# SevenSegClock.net
KiCad netlist of a schematic drawn in EAGLE
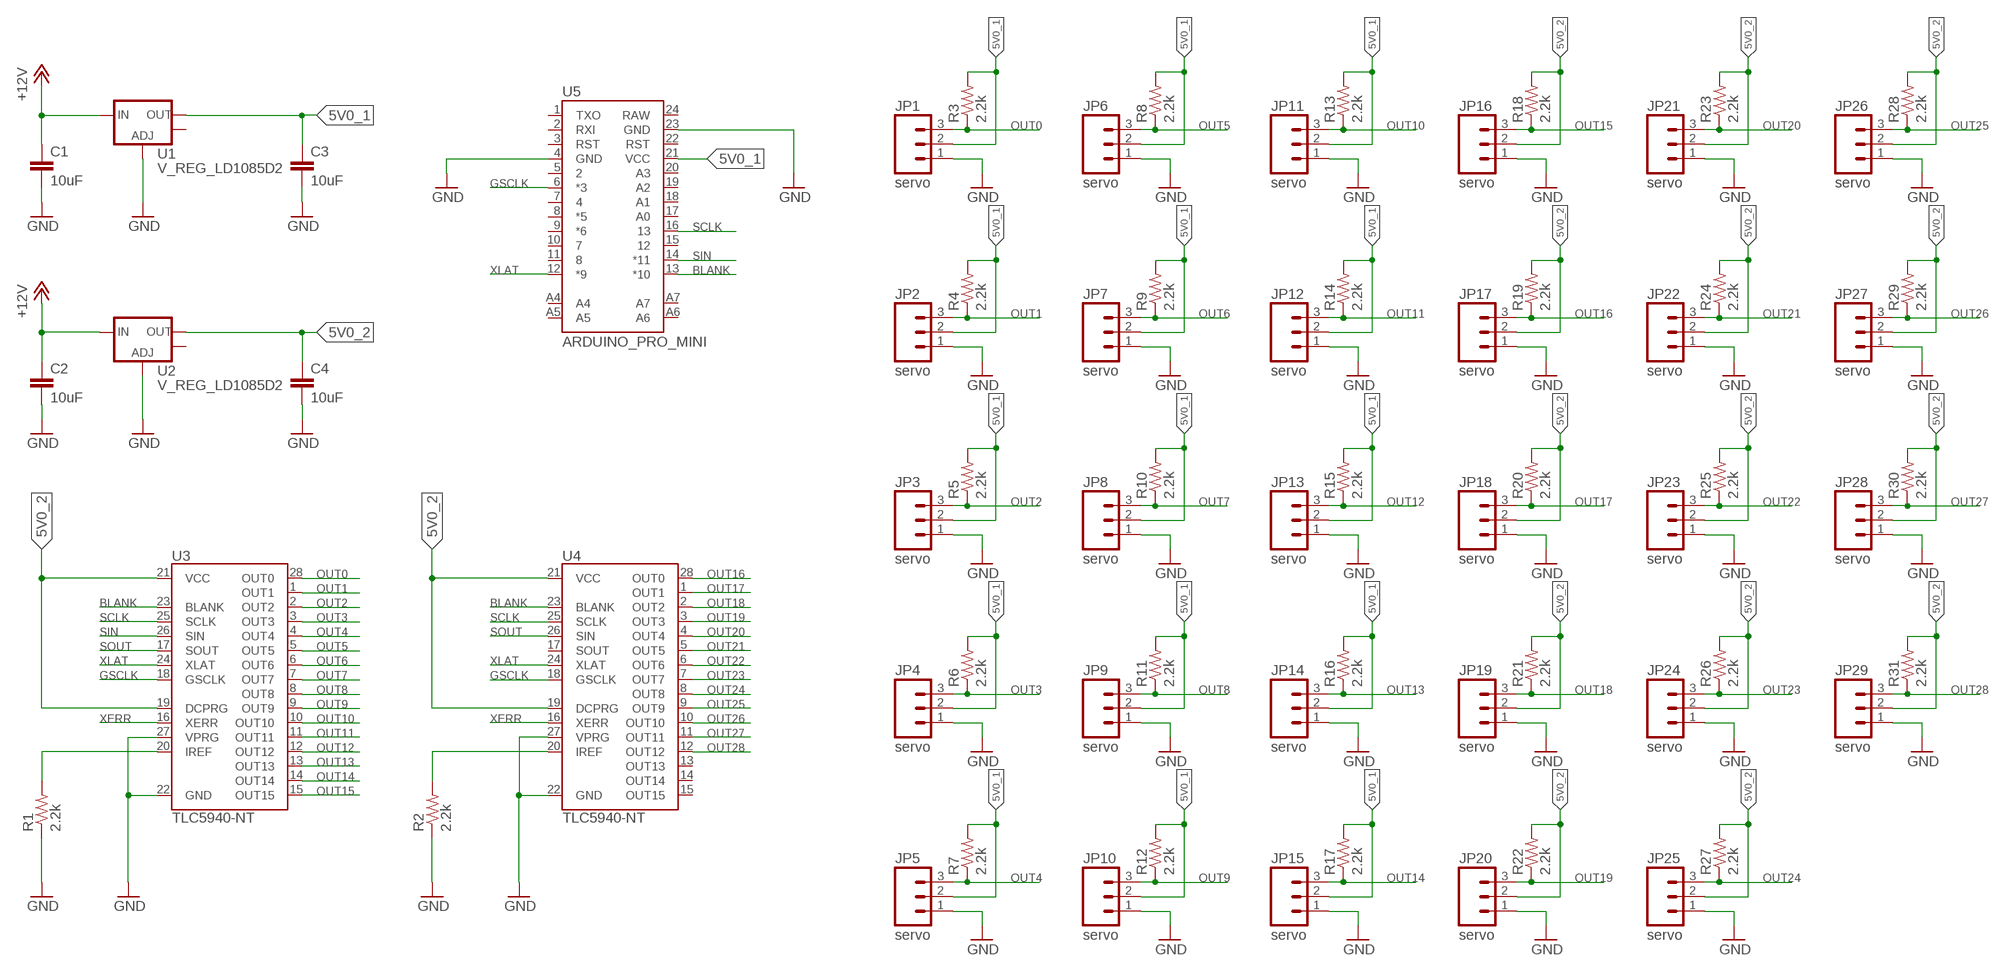
[diagram p0: schematic, sheet 1]

(export (version "E")
  (design (tool "Eeschema 10.0.6"))
  (components
    (comp (ref "C1")
      (value "10uF")
      (footprint "eagle-import:CAP-PTH-5MM")
      (libsource (lib "eagle-import") (part "CAPPTH1"))
    )
    (comp (ref "C2")
      (value "10uF")
      (footprint "eagle-import:CAP-PTH-5MM")
      (libsource (lib "eagle-import") (part "CAPPTH1"))
    )
    (comp (ref "C3")
      (value "10uF")
      (footprint "eagle-import:CAP-PTH-5MM")
      (libsource (lib "eagle-import") (part "CAPPTH1"))
    )
    (comp (ref "C4")
      (value "10uF")
      (footprint "eagle-import:CAP-PTH-5MM")
      (libsource (lib "eagle-import") (part "CAPPTH1"))
    )
    (comp (ref "JP1")
      (value "servo")
      (footprint "eagle-import:1X03")
      (libsource (lib "eagle-import") (part "M03PTH"))
    )
    (comp (ref "JP2")
      (value "servo")
      (footprint "eagle-import:1X03")
      (libsource (lib "eagle-import") (part "M03PTH"))
    )
    (comp (ref "JP3")
      (value "servo")
      (footprint "eagle-import:1X03")
      (libsource (lib "eagle-import") (part "M03PTH"))
    )
    (comp (ref "JP4")
      (value "servo")
      (footprint "eagle-import:1X03")
      (libsource (lib "eagle-import") (part "M03PTH"))
    )
    (comp (ref "JP5")
      (value "servo")
      (footprint "eagle-import:1X03")
      (libsource (lib "eagle-import") (part "M03PTH"))
    )
    (comp (ref "JP6")
      (value "servo")
      (footprint "eagle-import:1X03")
      (libsource (lib "eagle-import") (part "M03PTH"))
    )
    (comp (ref "JP7")
      (value "servo")
      (footprint "eagle-import:1X03")
      (libsource (lib "eagle-import") (part "M03PTH"))
    )
    (comp (ref "JP8")
      (value "servo")
      (footprint "eagle-import:1X03")
      (libsource (lib "eagle-import") (part "M03PTH"))
    )
    (comp (ref "JP9")
      (value "servo")
      (footprint "eagle-import:1X03")
      (libsource (lib "eagle-import") (part "M03PTH"))
    )
    (comp (ref "JP10")
      (value "servo")
      (footprint "eagle-import:1X03")
      (libsource (lib "eagle-import") (part "M03PTH"))
    )
    (comp (ref "JP11")
      (value "servo")
      (footprint "eagle-import:1X03")
      (libsource (lib "eagle-import") (part "M03PTH"))
    )
    (comp (ref "JP12")
      (value "servo")
      (footprint "eagle-import:1X03")
      (libsource (lib "eagle-import") (part "M03PTH"))
    )
    (comp (ref "JP13")
      (value "servo")
      (footprint "eagle-import:1X03")
      (libsource (lib "eagle-import") (part "M03PTH"))
    )
    (comp (ref "JP14")
      (value "servo")
      (footprint "eagle-import:1X03")
      (libsource (lib "eagle-import") (part "M03PTH"))
    )
    (comp (ref "JP15")
      (value "servo")
      (footprint "eagle-import:1X03")
      (libsource (lib "eagle-import") (part "M03PTH"))
    )
    (comp (ref "JP16")
      (value "servo")
      (footprint "eagle-import:1X03")
      (libsource (lib "eagle-import") (part "M03PTH"))
    )
    (comp (ref "JP17")
      (value "servo")
      (footprint "eagle-import:1X03")
      (libsource (lib "eagle-import") (part "M03PTH"))
    )
    (comp (ref "JP18")
      (value "servo")
      (footprint "eagle-import:1X03")
      (libsource (lib "eagle-import") (part "M03PTH"))
    )
    (comp (ref "JP19")
      (value "servo")
      (footprint "eagle-import:1X03")
      (libsource (lib "eagle-import") (part "M03PTH"))
    )
    (comp (ref "JP20")
      (value "servo")
      (footprint "eagle-import:1X03")
      (libsource (lib "eagle-import") (part "M03PTH"))
    )
    (comp (ref "JP21")
      (value "servo")
      (footprint "eagle-import:1X03")
      (libsource (lib "eagle-import") (part "M03PTH"))
    )
    (comp (ref "JP22")
      (value "servo")
      (footprint "eagle-import:1X03")
      (libsource (lib "eagle-import") (part "M03PTH"))
    )
    (comp (ref "JP23")
      (value "servo")
      (footprint "eagle-import:1X03")
      (libsource (lib "eagle-import") (part "M03PTH"))
    )
    (comp (ref "JP24")
      (value "servo")
      (footprint "eagle-import:1X03")
      (libsource (lib "eagle-import") (part "M03PTH"))
    )
    (comp (ref "JP25")
      (value "servo")
      (footprint "eagle-import:1X03")
      (libsource (lib "eagle-import") (part "M03PTH"))
    )
    (comp (ref "JP26")
      (value "servo")
      (footprint "eagle-import:1X03")
      (libsource (lib "eagle-import") (part "M03PTH"))
    )
    (comp (ref "JP27")
      (value "servo")
      (footprint "eagle-import:1X03")
      (libsource (lib "eagle-import") (part "M03PTH"))
    )
    (comp (ref "JP28")
      (value "servo")
      (footprint "eagle-import:1X03")
      (libsource (lib "eagle-import") (part "M03PTH"))
    )
    (comp (ref "JP29")
      (value "servo")
      (footprint "eagle-import:1X03")
      (libsource (lib "eagle-import") (part "M03PTH"))
    )
    (comp (ref "R1")
      (value "2.2k")
      (footprint "eagle-import:0204_5")
      (libsource (lib "eagle-import") (part "R-US_0204/5"))
    )
    (comp (ref "R2")
      (value "2.2k")
      (footprint "eagle-import:0204_5")
      (libsource (lib "eagle-import") (part "R-US_0204/5"))
    )
    (comp (ref "R3")
      (value "2.2k")
      (footprint "eagle-import:0204_5")
      (libsource (lib "eagle-import") (part "R-US_0204/5"))
    )
    (comp (ref "R4")
      (value "2.2k")
      (footprint "eagle-import:0204_5")
      (libsource (lib "eagle-import") (part "R-US_0204/5"))
    )
    (comp (ref "R5")
      (value "2.2k")
      (footprint "eagle-import:0204_5")
      (libsource (lib "eagle-import") (part "R-US_0204/5"))
    )
    (comp (ref "R6")
      (value "2.2k")
      (footprint "eagle-import:0204_5")
      (libsource (lib "eagle-import") (part "R-US_0204/5"))
    )
    (comp (ref "R7")
      (value "2.2k")
      (footprint "eagle-import:0204_5")
      (libsource (lib "eagle-import") (part "R-US_0204/5"))
    )
    (comp (ref "R8")
      (value "2.2k")
      (footprint "eagle-import:0204_5")
      (libsource (lib "eagle-import") (part "R-US_0204/5"))
    )
    (comp (ref "R9")
      (value "2.2k")
      (footprint "eagle-import:0204_5")
      (libsource (lib "eagle-import") (part "R-US_0204/5"))
    )
    (comp (ref "R10")
      (value "2.2k")
      (footprint "eagle-import:0204_5")
      (libsource (lib "eagle-import") (part "R-US_0204/5"))
    )
    (comp (ref "R11")
      (value "2.2k")
      (footprint "eagle-import:0204_5")
      (libsource (lib "eagle-import") (part "R-US_0204/5"))
    )
    (comp (ref "R12")
      (value "2.2k")
      (footprint "eagle-import:0204_5")
      (libsource (lib "eagle-import") (part "R-US_0204/5"))
    )
    (comp (ref "R13")
      (value "2.2k")
      (footprint "eagle-import:0204_5")
      (libsource (lib "eagle-import") (part "R-US_0204/5"))
    )
    (comp (ref "R14")
      (value "2.2k")
      (footprint "eagle-import:0204_5")
      (libsource (lib "eagle-import") (part "R-US_0204/5"))
    )
    (comp (ref "R15")
      (value "2.2k")
      (footprint "eagle-import:0204_5")
      (libsource (lib "eagle-import") (part "R-US_0204/5"))
    )
    (comp (ref "R16")
      (value "2.2k")
      (footprint "eagle-import:0204_5")
      (libsource (lib "eagle-import") (part "R-US_0204/5"))
    )
    (comp (ref "R17")
      (value "2.2k")
      (footprint "eagle-import:0204_5")
      (libsource (lib "eagle-import") (part "R-US_0204/5"))
    )
    (comp (ref "R18")
      (value "2.2k")
      (footprint "eagle-import:0204_5")
      (libsource (lib "eagle-import") (part "R-US_0204/5"))
    )
    (comp (ref "R19")
      (value "2.2k")
      (footprint "eagle-import:0204_5")
      (libsource (lib "eagle-import") (part "R-US_0204/5"))
    )
    (comp (ref "R20")
      (value "2.2k")
      (footprint "eagle-import:0204_5")
      (libsource (lib "eagle-import") (part "R-US_0204/5"))
    )
    (comp (ref "R21")
      (value "2.2k")
      (footprint "eagle-import:0204_5")
      (libsource (lib "eagle-import") (part "R-US_0204/5"))
    )
    (comp (ref "R22")
      (value "2.2k")
      (footprint "eagle-import:0204_5")
      (libsource (lib "eagle-import") (part "R-US_0204/5"))
    )
    (comp (ref "R23")
      (value "2.2k")
      (footprint "eagle-import:0204_5")
      (libsource (lib "eagle-import") (part "R-US_0204/5"))
    )
    (comp (ref "R24")
      (value "2.2k")
      (footprint "eagle-import:0204_5")
      (libsource (lib "eagle-import") (part "R-US_0204/5"))
    )
    (comp (ref "R25")
      (value "2.2k")
      (footprint "eagle-import:0204_5")
      (libsource (lib "eagle-import") (part "R-US_0204/5"))
    )
    (comp (ref "R26")
      (value "2.2k")
      (footprint "eagle-import:0204_5")
      (libsource (lib "eagle-import") (part "R-US_0204/5"))
    )
    (comp (ref "R27")
      (value "2.2k")
      (footprint "eagle-import:0204_5")
      (libsource (lib "eagle-import") (part "R-US_0204/5"))
    )
    (comp (ref "R28")
      (value "2.2k")
      (footprint "eagle-import:0204_5")
      (libsource (lib "eagle-import") (part "R-US_0204/5"))
    )
    (comp (ref "R29")
      (value "2.2k")
      (footprint "eagle-import:0204_5")
      (libsource (lib "eagle-import") (part "R-US_0204/5"))
    )
    (comp (ref "R30")
      (value "2.2k")
      (footprint "eagle-import:0204_5")
      (libsource (lib "eagle-import") (part "R-US_0204/5"))
    )
    (comp (ref "R31")
      (value "2.2k")
      (footprint "eagle-import:0204_5")
      (libsource (lib "eagle-import") (part "R-US_0204/5"))
    )
    (comp (ref "U1")
      (value "V_REG_LD1085D2")
      (footprint "eagle-import:D2PACK_A")
      (libsource (lib "eagle-import") (part "V_REG_LD1085D2"))
    )
    (comp (ref "U2")
      (value "V_REG_LD1085D2")
      (footprint "eagle-import:D2PACK_A")
      (libsource (lib "eagle-import") (part "V_REG_LD1085D2"))
    )
    (comp (ref "U3")
      (value "TLC5940-NT")
      (footprint "eagle-import:DIL28-3")
      (libsource (lib "eagle-import") (part "TLC5940-NT"))
    )
    (comp (ref "U4")
      (value "TLC5940-NT")
      (footprint "eagle-import:DIL28-3")
      (libsource (lib "eagle-import") (part "TLC5940-NT"))
    )
    (comp (ref "U5")
      (value "ARDUINO_PRO_MINI")
      (footprint "eagle-import:ARDUINO_PRO_MINI")
      (libsource (lib "eagle-import") (part "ARDUINO_PRO_MINI"))
    )
  )
  (nets
    (net (code "1") (name "+12V") (class "Default")
      (node (ref "C1") (pin "1") (pinfunction "1_1") (pintype "passive"))
      (node (ref "C2") (pin "1") (pinfunction "1_1") (pintype "passive"))
      (node (ref "U1") (pin "3") (pinfunction "IN_3") (pintype "input"))
      (node (ref "U2") (pin "3") (pinfunction "IN_3") (pintype "input"))
    )
    (net (code "2") (name "/BLANK") (class "Default")
      (node (ref "U3") (pin "23") (pinfunction "BLANK_23") (pintype "bidirectional"))
      (node (ref "U4") (pin "23") (pinfunction "BLANK_23") (pintype "bidirectional"))
      (node (ref "U5") (pin "13") (pinfunction "*10_13") (pintype "bidirectional"))
    )
    (net (code "3") (name "/GSCLK") (class "Default")
      (node (ref "U3") (pin "18") (pinfunction "GSCLK_18") (pintype "bidirectional"))
      (node (ref "U4") (pin "18") (pinfunction "GSCLK_18") (pintype "bidirectional"))
      (node (ref "U5") (pin "6") (pinfunction "*3_6") (pintype "bidirectional"))
    )
    (net (code "4") (name "/OUT0") (class "Default")
      (node (ref "JP1") (pin "3") (pinfunction "3_3") (pintype "passive"))
      (node (ref "R3") (pin "1") (pinfunction "1_1") (pintype "passive"))
      (node (ref "U3") (pin "28") (pinfunction "OUT0_28") (pintype "bidirectional"))
    )
    (net (code "5") (name "/OUT1") (class "Default")
      (node (ref "JP2") (pin "3") (pinfunction "3_3") (pintype "passive"))
      (node (ref "R4") (pin "1") (pinfunction "1_1") (pintype "passive"))
      (node (ref "U3") (pin "1") (pinfunction "OUT1_1") (pintype "bidirectional"))
    )
    (net (code "6") (name "/OUT2") (class "Default")
      (node (ref "JP3") (pin "3") (pinfunction "3_3") (pintype "passive"))
      (node (ref "R5") (pin "1") (pinfunction "1_1") (pintype "passive"))
      (node (ref "U3") (pin "2") (pinfunction "OUT2_2") (pintype "bidirectional"))
    )
    (net (code "7") (name "/OUT3") (class "Default")
      (node (ref "JP4") (pin "3") (pinfunction "3_3") (pintype "passive"))
      (node (ref "R6") (pin "1") (pinfunction "1_1") (pintype "passive"))
      (node (ref "U3") (pin "3") (pinfunction "OUT3_3") (pintype "bidirectional"))
    )
    (net (code "8") (name "/OUT4") (class "Default")
      (node (ref "JP5") (pin "3") (pinfunction "3_3") (pintype "passive"))
      (node (ref "R7") (pin "1") (pinfunction "1_1") (pintype "passive"))
      (node (ref "U3") (pin "4") (pinfunction "OUT4_4") (pintype "bidirectional"))
    )
    (net (code "9") (name "/OUT5") (class "Default")
      (node (ref "JP6") (pin "3") (pinfunction "3_3") (pintype "passive"))
      (node (ref "R8") (pin "1") (pinfunction "1_1") (pintype "passive"))
      (node (ref "U3") (pin "5") (pinfunction "OUT5_5") (pintype "bidirectional"))
    )
    (net (code "10") (name "/OUT6") (class "Default")
      (node (ref "JP7") (pin "3") (pinfunction "3_3") (pintype "passive"))
      (node (ref "R9") (pin "1") (pinfunction "1_1") (pintype "passive"))
      (node (ref "U3") (pin "6") (pinfunction "OUT6_6") (pintype "bidirectional"))
    )
    (net (code "11") (name "/OUT7") (class "Default")
      (node (ref "JP8") (pin "3") (pinfunction "3_3") (pintype "passive"))
      (node (ref "R10") (pin "1") (pinfunction "1_1") (pintype "passive"))
      (node (ref "U3") (pin "7") (pinfunction "OUT7_7") (pintype "bidirectional"))
    )
    (net (code "12") (name "/OUT8") (class "Default")
      (node (ref "JP9") (pin "3") (pinfunction "3_3") (pintype "passive"))
      (node (ref "R11") (pin "1") (pinfunction "1_1") (pintype "passive"))
      (node (ref "U3") (pin "8") (pinfunction "OUT8_8") (pintype "bidirectional"))
    )
    (net (code "13") (name "/OUT9") (class "Default")
      (node (ref "JP10") (pin "3") (pinfunction "3_3") (pintype "passive"))
      (node (ref "R12") (pin "1") (pinfunction "1_1") (pintype "passive"))
      (node (ref "U3") (pin "9") (pinfunction "OUT9_9") (pintype "bidirectional"))
    )
    (net (code "14") (name "/OUT10") (class "Default")
      (node (ref "JP11") (pin "3") (pinfunction "3_3") (pintype "passive"))
      (node (ref "R13") (pin "1") (pinfunction "1_1") (pintype "passive"))
      (node (ref "U3") (pin "10") (pinfunction "OUT10_10") (pintype "bidirectional"))
    )
    (net (code "15") (name "/OUT11") (class "Default")
      (node (ref "JP12") (pin "3") (pinfunction "3_3") (pintype "passive"))
      (node (ref "R14") (pin "1") (pinfunction "1_1") (pintype "passive"))
      (node (ref "U3") (pin "11") (pinfunction "OUT11_11") (pintype "bidirectional"))
    )
    (net (code "16") (name "/OUT12") (class "Default")
      (node (ref "JP13") (pin "3") (pinfunction "3_3") (pintype "passive"))
      (node (ref "R15") (pin "1") (pinfunction "1_1") (pintype "passive"))
      (node (ref "U3") (pin "12") (pinfunction "OUT12_12") (pintype "bidirectional"))
    )
    (net (code "17") (name "/OUT13") (class "Default")
      (node (ref "JP14") (pin "3") (pinfunction "3_3") (pintype "passive"))
      (node (ref "R16") (pin "1") (pinfunction "1_1") (pintype "passive"))
      (node (ref "U3") (pin "13") (pinfunction "OUT13_13") (pintype "bidirectional"))
    )
    (net (code "18") (name "/OUT14") (class "Default")
      (node (ref "JP15") (pin "3") (pinfunction "3_3") (pintype "passive"))
      (node (ref "R17") (pin "1") (pinfunction "1_1") (pintype "passive"))
      (node (ref "U3") (pin "14") (pinfunction "OUT14_14") (pintype "bidirectional"))
    )
    (net (code "19") (name "/OUT15") (class "Default")
      (node (ref "JP16") (pin "3") (pinfunction "3_3") (pintype "passive"))
      (node (ref "R18") (pin "1") (pinfunction "1_1") (pintype "passive"))
      (node (ref "U3") (pin "15") (pinfunction "OUT15_15") (pintype "bidirectional"))
    )
    (net (code "20") (name "/OUT16") (class "Default")
      (node (ref "JP17") (pin "3") (pinfunction "3_3") (pintype "passive"))
      (node (ref "R19") (pin "1") (pinfunction "1_1") (pintype "passive"))
      (node (ref "U4") (pin "28") (pinfunction "OUT0_28") (pintype "bidirectional"))
    )
    (net (code "21") (name "/OUT17") (class "Default")
      (node (ref "JP18") (pin "3") (pinfunction "3_3") (pintype "passive"))
      (node (ref "R20") (pin "1") (pinfunction "1_1") (pintype "passive"))
      (node (ref "U4") (pin "1") (pinfunction "OUT1_1") (pintype "bidirectional"))
    )
    (net (code "22") (name "/OUT18") (class "Default")
      (node (ref "JP19") (pin "3") (pinfunction "3_3") (pintype "passive"))
      (node (ref "R21") (pin "1") (pinfunction "1_1") (pintype "passive"))
      (node (ref "U4") (pin "2") (pinfunction "OUT2_2") (pintype "bidirectional"))
    )
    (net (code "23") (name "/OUT19") (class "Default")
      (node (ref "JP20") (pin "3") (pinfunction "3_3") (pintype "passive"))
      (node (ref "R22") (pin "1") (pinfunction "1_1") (pintype "passive"))
      (node (ref "U4") (pin "3") (pinfunction "OUT3_3") (pintype "bidirectional"))
    )
    (net (code "24") (name "/OUT20") (class "Default")
      (node (ref "JP21") (pin "3") (pinfunction "3_3") (pintype "passive"))
      (node (ref "R23") (pin "1") (pinfunction "1_1") (pintype "passive"))
      (node (ref "U4") (pin "4") (pinfunction "OUT4_4") (pintype "bidirectional"))
    )
    (net (code "25") (name "/OUT21") (class "Default")
      (node (ref "JP22") (pin "3") (pinfunction "3_3") (pintype "passive"))
      (node (ref "R24") (pin "1") (pinfunction "1_1") (pintype "passive"))
      (node (ref "U4") (pin "5") (pinfunction "OUT5_5") (pintype "bidirectional"))
    )
    (net (code "26") (name "/OUT22") (class "Default")
      (node (ref "JP23") (pin "3") (pinfunction "3_3") (pintype "passive"))
      (node (ref "R25") (pin "1") (pinfunction "1_1") (pintype "passive"))
      (node (ref "U4") (pin "6") (pinfunction "OUT6_6") (pintype "bidirectional"))
    )
    (net (code "27") (name "/OUT23") (class "Default")
      (node (ref "JP24") (pin "3") (pinfunction "3_3") (pintype "passive"))
      (node (ref "R26") (pin "1") (pinfunction "1_1") (pintype "passive"))
      (node (ref "U4") (pin "7") (pinfunction "OUT7_7") (pintype "bidirectional"))
    )
    (net (code "28") (name "/OUT24") (class "Default")
      (node (ref "JP25") (pin "3") (pinfunction "3_3") (pintype "passive"))
      (node (ref "R27") (pin "1") (pinfunction "1_1") (pintype "passive"))
      (node (ref "U4") (pin "8") (pinfunction "OUT8_8") (pintype "bidirectional"))
    )
    (net (code "29") (name "/OUT25") (class "Default")
      (node (ref "JP26") (pin "3") (pinfunction "3_3") (pintype "passive"))
      (node (ref "R28") (pin "1") (pinfunction "1_1") (pintype "passive"))
      (node (ref "U4") (pin "9") (pinfunction "OUT9_9") (pintype "bidirectional"))
    )
    (net (code "30") (name "/OUT26") (class "Default")
      (node (ref "JP27") (pin "3") (pinfunction "3_3") (pintype "passive"))
      (node (ref "R29") (pin "1") (pinfunction "1_1") (pintype "passive"))
      (node (ref "U4") (pin "10") (pinfunction "OUT10_10") (pintype "bidirectional"))
    )
    (net (code "31") (name "/OUT27") (class "Default")
      (node (ref "JP28") (pin "3") (pinfunction "3_3") (pintype "passive"))
      (node (ref "R30") (pin "1") (pinfunction "1_1") (pintype "passive"))
      (node (ref "U4") (pin "11") (pinfunction "OUT11_11") (pintype "bidirectional"))
    )
    (net (code "32") (name "/OUT28") (class "Default")
      (node (ref "JP29") (pin "3") (pinfunction "3_3") (pintype "passive"))
      (node (ref "R31") (pin "1") (pinfunction "1_1") (pintype "passive"))
      (node (ref "U4") (pin "12") (pinfunction "OUT12_12") (pintype "bidirectional"))
    )
    (net (code "33") (name "/SCLK") (class "Default")
      (node (ref "U3") (pin "25") (pinfunction "SCLK_25") (pintype "bidirectional"))
      (node (ref "U4") (pin "25") (pinfunction "SCLK_25") (pintype "bidirectional"))
      (node (ref "U5") (pin "16") (pinfunction "13_16") (pintype "bidirectional"))
    )
    (net (code "34") (name "/SIN") (class "Default")
      (node (ref "U3") (pin "26") (pinfunction "SIN_26") (pintype "bidirectional"))
      (node (ref "U5") (pin "14") (pinfunction "*11_14") (pintype "bidirectional"))
    )
    (net (code "35") (name "/SOUT") (class "Default")
      (node (ref "U3") (pin "17") (pinfunction "SOUT_17") (pintype "bidirectional"))
      (node (ref "U4") (pin "26") (pinfunction "SIN_26") (pintype "bidirectional"))
    )
    (net (code "36") (name "/XERR") (class "Default")
      (node (ref "U3") (pin "16") (pinfunction "XERR_16") (pintype "bidirectional"))
      (node (ref "U4") (pin "16") (pinfunction "XERR_16") (pintype "bidirectional"))
    )
    (net (code "37") (name "/XLAT") (class "Default")
      (node (ref "U3") (pin "24") (pinfunction "XLAT_24") (pintype "bidirectional"))
      (node (ref "U4") (pin "24") (pinfunction "XLAT_24") (pintype "bidirectional"))
      (node (ref "U5") (pin "12") (pinfunction "*9_12") (pintype "bidirectional"))
    )
    (net (code "38") (name "5V0_1") (class "Default")
      (node (ref "C3") (pin "1") (pinfunction "1_1") (pintype "passive"))
      (node (ref "JP1") (pin "2") (pinfunction "2_2") (pintype "passive"))
      (node (ref "JP10") (pin "2") (pinfunction "2_2") (pintype "passive"))
      (node (ref "JP11") (pin "2") (pinfunction "2_2") (pintype "passive"))
      (node (ref "JP12") (pin "2") (pinfunction "2_2") (pintype "passive"))
      (node (ref "JP13") (pin "2") (pinfunction "2_2") (pintype "passive"))
      (node (ref "JP14") (pin "2") (pinfunction "2_2") (pintype "passive"))
      (node (ref "JP15") (pin "2") (pinfunction "2_2") (pintype "passive"))
      (node (ref "JP2") (pin "2") (pinfunction "2_2") (pintype "passive"))
      (node (ref "JP3") (pin "2") (pinfunction "2_2") (pintype "passive"))
      (node (ref "JP4") (pin "2") (pinfunction "2_2") (pintype "passive"))
      (node (ref "JP5") (pin "2") (pinfunction "2_2") (pintype "passive"))
      (node (ref "JP6") (pin "2") (pinfunction "2_2") (pintype "passive"))
      (node (ref "JP7") (pin "2") (pinfunction "2_2") (pintype "passive"))
      (node (ref "JP8") (pin "2") (pinfunction "2_2") (pintype "passive"))
      (node (ref "JP9") (pin "2") (pinfunction "2_2") (pintype "passive"))
      (node (ref "R10") (pin "2") (pinfunction "2_2") (pintype "passive"))
      (node (ref "R11") (pin "2") (pinfunction "2_2") (pintype "passive"))
      (node (ref "R12") (pin "2") (pinfunction "2_2") (pintype "passive"))
      (node (ref "R13") (pin "2") (pinfunction "2_2") (pintype "passive"))
      (node (ref "R14") (pin "2") (pinfunction "2_2") (pintype "passive"))
      (node (ref "R15") (pin "2") (pinfunction "2_2") (pintype "passive"))
      (node (ref "R16") (pin "2") (pinfunction "2_2") (pintype "passive"))
      (node (ref "R17") (pin "2") (pinfunction "2_2") (pintype "passive"))
      (node (ref "R3") (pin "2") (pinfunction "2_2") (pintype "passive"))
      (node (ref "R4") (pin "2") (pinfunction "2_2") (pintype "passive"))
      (node (ref "R5") (pin "2") (pinfunction "2_2") (pintype "passive"))
      (node (ref "R6") (pin "2") (pinfunction "2_2") (pintype "passive"))
      (node (ref "R7") (pin "2") (pinfunction "2_2") (pintype "passive"))
      (node (ref "R8") (pin "2") (pinfunction "2_2") (pintype "passive"))
      (node (ref "R9") (pin "2") (pinfunction "2_2") (pintype "passive"))
      (node (ref "U1") (pin "2") (pinfunction "OUT_2") (pintype "output"))
      (node (ref "U5") (pin "21") (pinfunction "VCC_21") (pintype "bidirectional"))
    )
    (net (code "39") (name "5V0_2") (class "Default")
      (node (ref "C4") (pin "1") (pinfunction "1_1") (pintype "passive"))
      (node (ref "JP16") (pin "2") (pinfunction "2_2") (pintype "passive"))
      (node (ref "JP17") (pin "2") (pinfunction "2_2") (pintype "passive"))
      (node (ref "JP18") (pin "2") (pinfunction "2_2") (pintype "passive"))
      (node (ref "JP19") (pin "2") (pinfunction "2_2") (pintype "passive"))
      (node (ref "JP20") (pin "2") (pinfunction "2_2") (pintype "passive"))
      (node (ref "JP21") (pin "2") (pinfunction "2_2") (pintype "passive"))
      (node (ref "JP22") (pin "2") (pinfunction "2_2") (pintype "passive"))
      (node (ref "JP23") (pin "2") (pinfunction "2_2") (pintype "passive"))
      (node (ref "JP24") (pin "2") (pinfunction "2_2") (pintype "passive"))
      (node (ref "JP25") (pin "2") (pinfunction "2_2") (pintype "passive"))
      (node (ref "JP26") (pin "2") (pinfunction "2_2") (pintype "passive"))
      (node (ref "JP27") (pin "2") (pinfunction "2_2") (pintype "passive"))
      (node (ref "JP28") (pin "2") (pinfunction "2_2") (pintype "passive"))
      (node (ref "JP29") (pin "2") (pinfunction "2_2") (pintype "passive"))
      (node (ref "R18") (pin "2") (pinfunction "2_2") (pintype "passive"))
      (node (ref "R19") (pin "2") (pinfunction "2_2") (pintype "passive"))
      (node (ref "R20") (pin "2") (pinfunction "2_2") (pintype "passive"))
      (node (ref "R21") (pin "2") (pinfunction "2_2") (pintype "passive"))
      (node (ref "R22") (pin "2") (pinfunction "2_2") (pintype "passive"))
      (node (ref "R23") (pin "2") (pinfunction "2_2") (pintype "passive"))
      (node (ref "R24") (pin "2") (pinfunction "2_2") (pintype "passive"))
      (node (ref "R25") (pin "2") (pinfunction "2_2") (pintype "passive"))
      (node (ref "R26") (pin "2") (pinfunction "2_2") (pintype "passive"))
      (node (ref "R27") (pin "2") (pinfunction "2_2") (pintype "passive"))
      (node (ref "R28") (pin "2") (pinfunction "2_2") (pintype "passive"))
      (node (ref "R29") (pin "2") (pinfunction "2_2") (pintype "passive"))
      (node (ref "R30") (pin "2") (pinfunction "2_2") (pintype "passive"))
      (node (ref "R31") (pin "2") (pinfunction "2_2") (pintype "passive"))
      (node (ref "U2") (pin "2") (pinfunction "OUT_2") (pintype "output"))
      (node (ref "U3") (pin "19") (pinfunction "DCPRG_19") (pintype "bidirectional"))
      (node (ref "U3") (pin "21") (pinfunction "VCC_21") (pintype "bidirectional"))
      (node (ref "U4") (pin "19") (pinfunction "DCPRG_19") (pintype "bidirectional"))
      (node (ref "U4") (pin "21") (pinfunction "VCC_21") (pintype "bidirectional"))
    )
    (net (code "40") (name "GND") (class "Default")
      (node (ref "C1") (pin "2") (pinfunction "2_2") (pintype "passive"))
      (node (ref "C2") (pin "2") (pinfunction "2_2") (pintype "passive"))
      (node (ref "C3") (pin "2") (pinfunction "2_2") (pintype "passive"))
      (node (ref "C4") (pin "2") (pinfunction "2_2") (pintype "passive"))
      (node (ref "JP1") (pin "1") (pinfunction "1_1") (pintype "passive"))
      (node (ref "JP10") (pin "1") (pinfunction "1_1") (pintype "passive"))
      (node (ref "JP11") (pin "1") (pinfunction "1_1") (pintype "passive"))
      (node (ref "JP12") (pin "1") (pinfunction "1_1") (pintype "passive"))
      (node (ref "JP13") (pin "1") (pinfunction "1_1") (pintype "passive"))
      (node (ref "JP14") (pin "1") (pinfunction "1_1") (pintype "passive"))
      (node (ref "JP15") (pin "1") (pinfunction "1_1") (pintype "passive"))
      (node (ref "JP16") (pin "1") (pinfunction "1_1") (pintype "passive"))
      (node (ref "JP17") (pin "1") (pinfunction "1_1") (pintype "passive"))
      (node (ref "JP18") (pin "1") (pinfunction "1_1") (pintype "passive"))
      (node (ref "JP19") (pin "1") (pinfunction "1_1") (pintype "passive"))
      (node (ref "JP2") (pin "1") (pinfunction "1_1") (pintype "passive"))
      (node (ref "JP20") (pin "1") (pinfunction "1_1") (pintype "passive"))
      (node (ref "JP21") (pin "1") (pinfunction "1_1") (pintype "passive"))
      (node (ref "JP22") (pin "1") (pinfunction "1_1") (pintype "passive"))
      (node (ref "JP23") (pin "1") (pinfunction "1_1") (pintype "passive"))
      (node (ref "JP24") (pin "1") (pinfunction "1_1") (pintype "passive"))
      (node (ref "JP25") (pin "1") (pinfunction "1_1") (pintype "passive"))
      (node (ref "JP26") (pin "1") (pinfunction "1_1") (pintype "passive"))
      (node (ref "JP27") (pin "1") (pinfunction "1_1") (pintype "passive"))
      (node (ref "JP28") (pin "1") (pinfunction "1_1") (pintype "passive"))
      (node (ref "JP29") (pin "1") (pinfunction "1_1") (pintype "passive"))
      (node (ref "JP3") (pin "1") (pinfunction "1_1") (pintype "passive"))
      (node (ref "JP4") (pin "1") (pinfunction "1_1") (pintype "passive"))
      (node (ref "JP5") (pin "1") (pinfunction "1_1") (pintype "passive"))
      (node (ref "JP6") (pin "1") (pinfunction "1_1") (pintype "passive"))
      (node (ref "JP7") (pin "1") (pinfunction "1_1") (pintype "passive"))
      (node (ref "JP8") (pin "1") (pinfunction "1_1") (pintype "passive"))
      (node (ref "JP9") (pin "1") (pinfunction "1_1") (pintype "passive"))
      (node (ref "R1") (pin "1") (pinfunction "1_1") (pintype "passive"))
      (node (ref "R2") (pin "1") (pinfunction "1_1") (pintype "passive"))
      (node (ref "U1") (pin "1") (pinfunction "ADJ_1") (pintype "input"))
      (node (ref "U2") (pin "1") (pinfunction "ADJ_1") (pintype "input"))
      (node (ref "U3") (pin "22") (pinfunction "GND_22") (pintype "bidirectional"))
      (node (ref "U3") (pin "27") (pinfunction "VPRG_27") (pintype "bidirectional"))
      (node (ref "U4") (pin "22") (pinfunction "GND_22") (pintype "bidirectional"))
      (node (ref "U4") (pin "27") (pinfunction "VPRG_27") (pintype "bidirectional"))
      (node (ref "U5") (pin "23") (pinfunction "GND_23") (pintype "bidirectional"))
      (node (ref "U5") (pin "4") (pinfunction "GND_4") (pintype "bidirectional"))
    )
    (net (code "41") (name "Net-(U3-IREF)") (class "Default")
      (node (ref "R1") (pin "2") (pinfunction "2_2") (pintype "passive"))
      (node (ref "U3") (pin "20") (pinfunction "IREF_20") (pintype "bidirectional"))
    )
    (net (code "42") (name "Net-(U4-IREF)") (class "Default")
      (node (ref "R2") (pin "2") (pinfunction "2_2") (pintype "passive"))
      (node (ref "U4") (pin "20") (pinfunction "IREF_20") (pintype "bidirectional"))
    )
    (net (code "43") (name "unconnected-(U1-OUT-PadTAB)") (class "Default")
      (node (ref "U1") (pin "TAB") (pinfunction "OUT_TAB") (pintype "output"))
    )
    (net (code "44") (name "unconnected-(U2-OUT-PadTAB)") (class "Default")
      (node (ref "U2") (pin "TAB") (pinfunction "OUT_TAB") (pintype "output"))
    )
    (net (code "45") (name "unconnected-(U4-OUT13-Pad13)") (class "Default")
      (node (ref "U4") (pin "13") (pinfunction "OUT13_13") (pintype "bidirectional"))
    )
    (net (code "46") (name "unconnected-(U4-OUT14-Pad14)") (class "Default")
      (node (ref "U4") (pin "14") (pinfunction "OUT14_14") (pintype "bidirectional"))
    )
    (net (code "47") (name "unconnected-(U4-OUT15-Pad15)") (class "Default")
      (node (ref "U4") (pin "15") (pinfunction "OUT15_15") (pintype "bidirectional"))
    )
    (net (code "48") (name "unconnected-(U4-SOUT-Pad17)") (class "Default")
      (node (ref "U4") (pin "17") (pinfunction "SOUT_17") (pintype "bidirectional"))
    )
    (net (code "49") (name "unconnected-(U5-*5-Pad8)") (class "Default")
      (node (ref "U5") (pin "8") (pinfunction "*5_8") (pintype "bidirectional"))
    )
    (net (code "50") (name "unconnected-(U5-*6-Pad9)") (class "Default")
      (node (ref "U5") (pin "9") (pinfunction "*6_9") (pintype "bidirectional"))
    )
    (net (code "51") (name "unconnected-(U5-2-Pad5)") (class "Default")
      (node (ref "U5") (pin "5") (pinfunction "2_5") (pintype "bidirectional"))
    )
    (net (code "52") (name "unconnected-(U5-4-Pad7)") (class "Default")
      (node (ref "U5") (pin "7") (pinfunction "4_7") (pintype "bidirectional"))
    )
    (net (code "53") (name "unconnected-(U5-7-Pad10)") (class "Default")
      (node (ref "U5") (pin "10") (pinfunction "7_10") (pintype "bidirectional"))
    )
    (net (code "54") (name "unconnected-(U5-8-Pad11)") (class "Default")
      (node (ref "U5") (pin "11") (pinfunction "8_11") (pintype "bidirectional"))
    )
    (net (code "55") (name "unconnected-(U5-12-Pad15)") (class "Default")
      (node (ref "U5") (pin "15") (pinfunction "12_15") (pintype "bidirectional"))
    )
    (net (code "56") (name "unconnected-(U5-A0-Pad17)") (class "Default")
      (node (ref "U5") (pin "17") (pinfunction "A0_17") (pintype "bidirectional"))
    )
    (net (code "57") (name "unconnected-(U5-A1-Pad18)") (class "Default")
      (node (ref "U5") (pin "18") (pinfunction "A1_18") (pintype "bidirectional"))
    )
    (net (code "58") (name "unconnected-(U5-A2-Pad19)") (class "Default")
      (node (ref "U5") (pin "19") (pinfunction "A2_19") (pintype "bidirectional"))
    )
    (net (code "59") (name "unconnected-(U5-A3-Pad20)") (class "Default")
      (node (ref "U5") (pin "20") (pinfunction "A3_20") (pintype "bidirectional"))
    )
    (net (code "60") (name "unconnected-(U5-PadA4)") (class "Default")
      (node (ref "U5") (pin "A4") (pinfunction "A4_A4") (pintype "bidirectional"))
    )
    (net (code "61") (name "unconnected-(U5-PadA5)") (class "Default")
      (node (ref "U5") (pin "A5") (pinfunction "A5_A5") (pintype "bidirectional"))
    )
    (net (code "62") (name "unconnected-(U5-PadA6)") (class "Default")
      (node (ref "U5") (pin "A6") (pinfunction "A6_A6") (pintype "bidirectional"))
    )
    (net (code "63") (name "unconnected-(U5-PadA7)") (class "Default")
      (node (ref "U5") (pin "A7") (pinfunction "A7_A7") (pintype "bidirectional"))
    )
    (net (code "64") (name "unconnected-(U5-RAW-Pad24)") (class "Default")
      (node (ref "U5") (pin "24") (pinfunction "RAW_24") (pintype "bidirectional"))
    )
    (net (code "65") (name "unconnected-(U5-RST-Pad3)") (class "Default")
      (node (ref "U5") (pin "3") (pinfunction "RST_3") (pintype "bidirectional"))
    )
    (net (code "66") (name "unconnected-(U5-RST-Pad22)") (class "Default")
      (node (ref "U5") (pin "22") (pinfunction "RST_22") (pintype "bidirectional"))
    )
    (net (code "67") (name "unconnected-(U5-RXI-Pad2)") (class "Default")
      (node (ref "U5") (pin "2") (pinfunction "RXI_2") (pintype "bidirectional"))
    )
    (net (code "68") (name "unconnected-(U5-TXO-Pad1)") (class "Default")
      (node (ref "U5") (pin "1") (pinfunction "TXO_1") (pintype "bidirectional"))
    )
  )
)
